# afig-adaptor.net
KiCad netlist of a schematic drawn in EAGLE
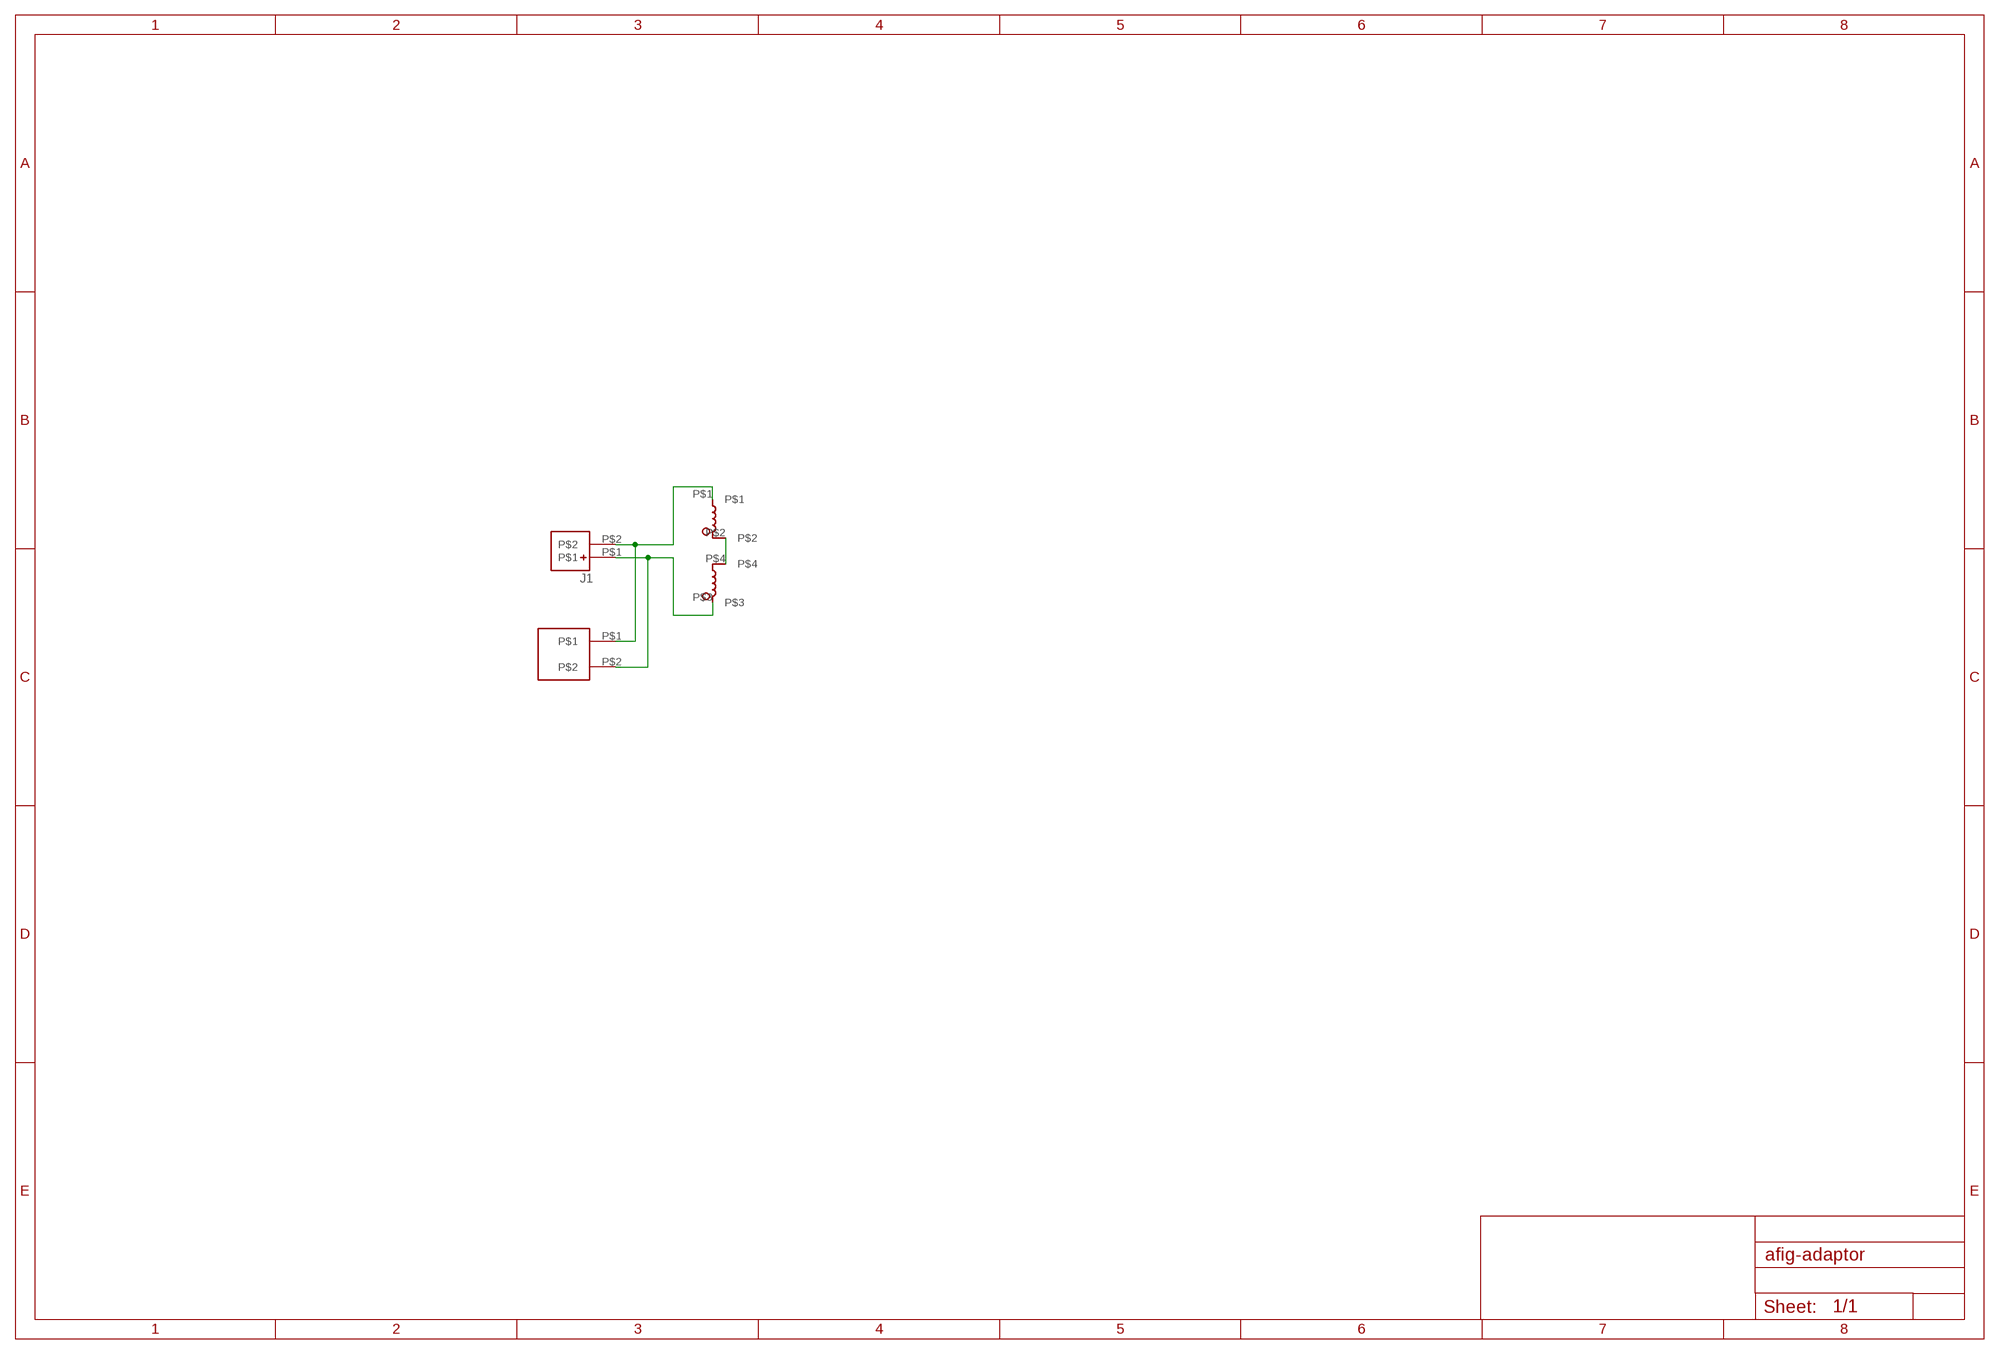
[diagram p0: schematic, sheet 1]

(export (version "E")
  (design (tool "Eeschema 10.0.6"))
  (components
    (comp (ref "J1")
      (value "B2B-PH-SM4-TB")
      (footprint "eagle-import:B2B-PH-SM4-TB")
      (libsource (lib "eagle-import") (part "B2B-PH-SM4-TB"))
    )
    (comp (ref "U$1")
      (value "AFIG-0007")
      (footprint "eagle-import:AFIG-0007")
      (libsource (lib "eagle-import") (part "AFIG-0007"))
    )
    (comp (ref "U$2")
      (value "0878580002")
      (footprint "eagle-import:0878580002")
      (libsource (lib "eagle-import") (part "0878580002"))
    )
  )
  (nets
    (net (code "1") (name "Net-(J1-PadP$1)") (class "Default")
      (node (ref "J1") (pin "P$1") (pinfunction "P$1_P$1") (pintype "bidirectional"))
      (node (ref "U$1") (pin "P$3") (pinfunction "P$3_P$3") (pintype "bidirectional"))
      (node (ref "U$2") (pin "P$2") (pinfunction "P$2_P$2") (pintype "bidirectional"))
    )
    (net (code "2") (name "Net-(J1-PadP$2)") (class "Default")
      (node (ref "J1") (pin "P$2") (pinfunction "P$2_P$2") (pintype "bidirectional"))
      (node (ref "U$1") (pin "P$1") (pinfunction "P$1_P$1") (pintype "bidirectional"))
      (node (ref "U$2") (pin "P$1") (pinfunction "P$1_P$1") (pintype "bidirectional"))
    )
    (net (code "3") (name "Net-(U$1-PadP$2)") (class "Default")
      (node (ref "U$1") (pin "P$2") (pinfunction "P$2_P$2") (pintype "bidirectional"))
      (node (ref "U$1") (pin "P$4") (pinfunction "P$4_P$4") (pintype "bidirectional"))
    )
  )
)
